# picoKey_230407.net
KiCad netlist of a schematic drawn in EAGLE
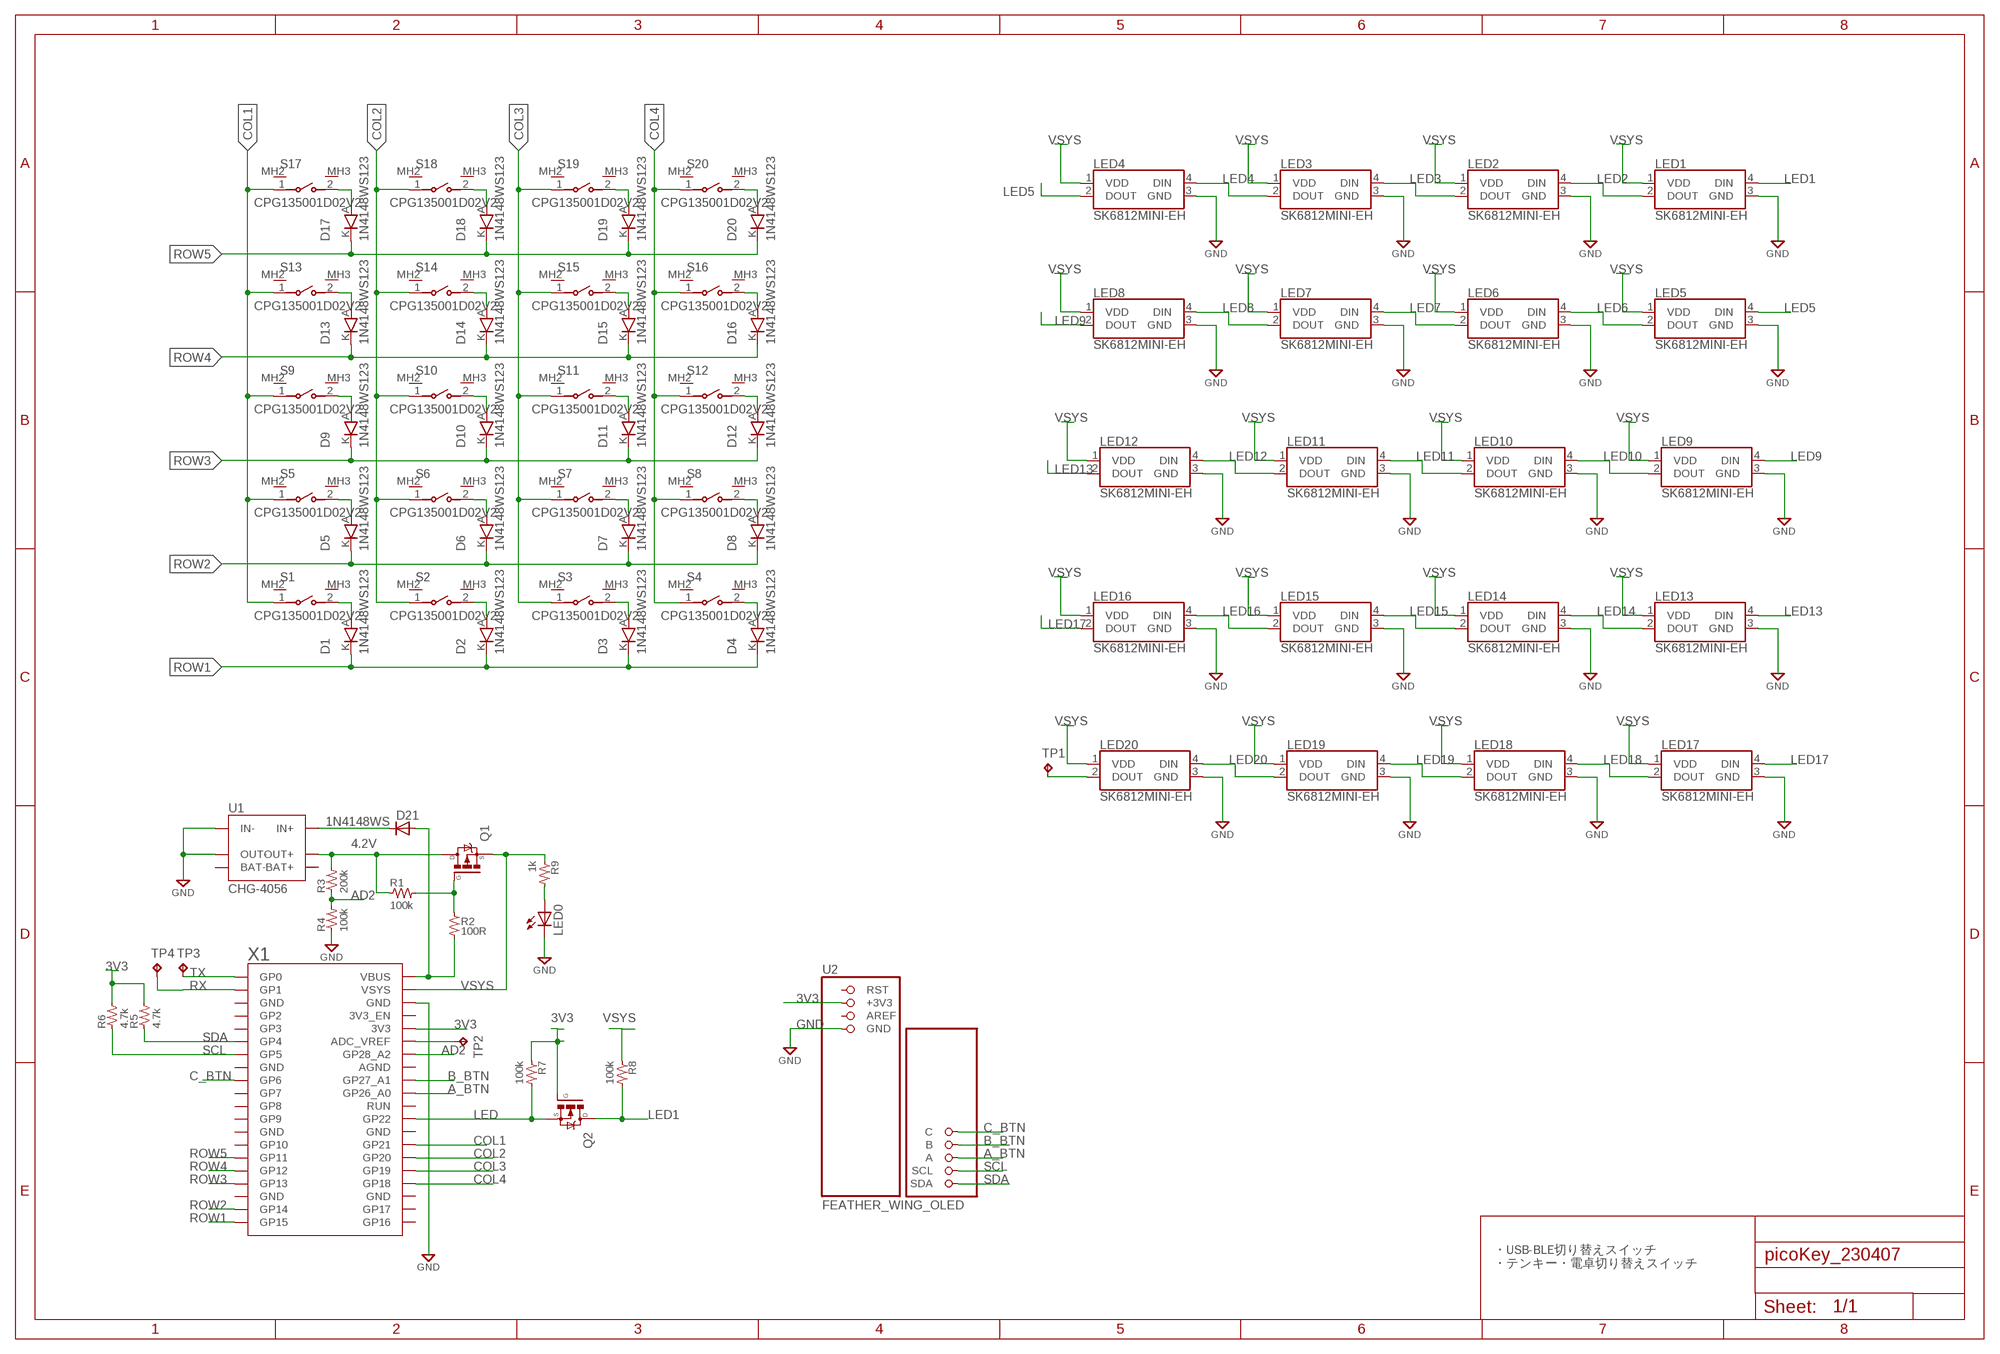
[diagram p0: schematic, sheet 1]

(export (version "E")
  (design (tool "Eeschema 10.0.6"))
  (components
    (comp (ref "D1")
      (value "1N4148WS123")
      (footprint "eagle-import:SOD-123")
      (libsource (lib "eagle-import") (part "1N4148WS123"))
    )
    (comp (ref "D2")
      (value "1N4148WS123")
      (footprint "eagle-import:SOD-123")
      (libsource (lib "eagle-import") (part "1N4148WS123"))
    )
    (comp (ref "D3")
      (value "1N4148WS123")
      (footprint "eagle-import:SOD-123")
      (libsource (lib "eagle-import") (part "1N4148WS123"))
    )
    (comp (ref "D4")
      (value "1N4148WS123")
      (footprint "eagle-import:SOD-123")
      (libsource (lib "eagle-import") (part "1N4148WS123"))
    )
    (comp (ref "D5")
      (value "1N4148WS123")
      (footprint "eagle-import:SOD-123")
      (libsource (lib "eagle-import") (part "1N4148WS123"))
    )
    (comp (ref "D6")
      (value "1N4148WS123")
      (footprint "eagle-import:SOD-123")
      (libsource (lib "eagle-import") (part "1N4148WS123"))
    )
    (comp (ref "D7")
      (value "1N4148WS123")
      (footprint "eagle-import:SOD-123")
      (libsource (lib "eagle-import") (part "1N4148WS123"))
    )
    (comp (ref "D8")
      (value "1N4148WS123")
      (footprint "eagle-import:SOD-123")
      (libsource (lib "eagle-import") (part "1N4148WS123"))
    )
    (comp (ref "D9")
      (value "1N4148WS123")
      (footprint "eagle-import:SOD-123")
      (libsource (lib "eagle-import") (part "1N4148WS123"))
    )
    (comp (ref "D10")
      (value "1N4148WS123")
      (footprint "eagle-import:SOD-123")
      (libsource (lib "eagle-import") (part "1N4148WS123"))
    )
    (comp (ref "D11")
      (value "1N4148WS123")
      (footprint "eagle-import:SOD-123")
      (libsource (lib "eagle-import") (part "1N4148WS123"))
    )
    (comp (ref "D12")
      (value "1N4148WS123")
      (footprint "eagle-import:SOD-123")
      (libsource (lib "eagle-import") (part "1N4148WS123"))
    )
    (comp (ref "D13")
      (value "1N4148WS123")
      (footprint "eagle-import:SOD-123")
      (libsource (lib "eagle-import") (part "1N4148WS123"))
    )
    (comp (ref "D14")
      (value "1N4148WS123")
      (footprint "eagle-import:SOD-123")
      (libsource (lib "eagle-import") (part "1N4148WS123"))
    )
    (comp (ref "D15")
      (value "1N4148WS123")
      (footprint "eagle-import:SOD-123")
      (libsource (lib "eagle-import") (part "1N4148WS123"))
    )
    (comp (ref "D16")
      (value "1N4148WS123")
      (footprint "eagle-import:SOD-123")
      (libsource (lib "eagle-import") (part "1N4148WS123"))
    )
    (comp (ref "D17")
      (value "1N4148WS123")
      (footprint "eagle-import:SOD-123")
      (libsource (lib "eagle-import") (part "1N4148WS123"))
    )
    (comp (ref "D18")
      (value "1N4148WS123")
      (footprint "eagle-import:SOD-123")
      (libsource (lib "eagle-import") (part "1N4148WS123"))
    )
    (comp (ref "D19")
      (value "1N4148WS123")
      (footprint "eagle-import:SOD-123")
      (libsource (lib "eagle-import") (part "1N4148WS123"))
    )
    (comp (ref "D20")
      (value "1N4148WS123")
      (footprint "eagle-import:SOD-123")
      (libsource (lib "eagle-import") (part "1N4148WS123"))
    )
    (comp (ref "D21")
      (value "1N4148WS")
      (footprint "eagle-import:SOD-123")
      (libsource (lib "eagle-import") (part "DIODE123"))
    )
    (comp (ref "LED0")
      (value "LEDCHIP-LED0603")
      (footprint "eagle-import:CHIP-LED0603")
      (libsource (lib "eagle-import") (part "LEDCHIP-LED0603"))
    )
    (comp (ref "LED1")
      (value "SK6812MINI-EH")
      (footprint "eagle-import:SK6812MINIE-H")
      (libsource (lib "eagle-import") (part "SK6812MINI-EH"))
    )
    (comp (ref "LED2")
      (value "SK6812MINI-EH")
      (footprint "eagle-import:SK6812MINIE-H")
      (libsource (lib "eagle-import") (part "SK6812MINI-EH"))
    )
    (comp (ref "LED3")
      (value "SK6812MINI-EH")
      (footprint "eagle-import:SK6812MINIE-H")
      (libsource (lib "eagle-import") (part "SK6812MINI-EH"))
    )
    (comp (ref "LED4")
      (value "SK6812MINI-EH")
      (footprint "eagle-import:SK6812MINIE-H")
      (libsource (lib "eagle-import") (part "SK6812MINI-EH"))
    )
    (comp (ref "LED5")
      (value "SK6812MINI-EH")
      (footprint "eagle-import:SK6812MINIE-H")
      (libsource (lib "eagle-import") (part "SK6812MINI-EH"))
    )
    (comp (ref "LED6")
      (value "SK6812MINI-EH")
      (footprint "eagle-import:SK6812MINIE-H")
      (libsource (lib "eagle-import") (part "SK6812MINI-EH"))
    )
    (comp (ref "LED7")
      (value "SK6812MINI-EH")
      (footprint "eagle-import:SK6812MINIE-H")
      (libsource (lib "eagle-import") (part "SK6812MINI-EH"))
    )
    (comp (ref "LED8")
      (value "SK6812MINI-EH")
      (footprint "eagle-import:SK6812MINIE-H")
      (libsource (lib "eagle-import") (part "SK6812MINI-EH"))
    )
    (comp (ref "LED9")
      (value "SK6812MINI-EH")
      (footprint "eagle-import:SK6812MINIE-H")
      (libsource (lib "eagle-import") (part "SK6812MINI-EH"))
    )
    (comp (ref "LED10")
      (value "SK6812MINI-EH")
      (footprint "eagle-import:SK6812MINIE-H")
      (libsource (lib "eagle-import") (part "SK6812MINI-EH"))
    )
    (comp (ref "LED11")
      (value "SK6812MINI-EH")
      (footprint "eagle-import:SK6812MINIE-H")
      (libsource (lib "eagle-import") (part "SK6812MINI-EH"))
    )
    (comp (ref "LED12")
      (value "SK6812MINI-EH")
      (footprint "eagle-import:SK6812MINIE-H")
      (libsource (lib "eagle-import") (part "SK6812MINI-EH"))
    )
    (comp (ref "LED13")
      (value "SK6812MINI-EH")
      (footprint "eagle-import:SK6812MINIE-H")
      (libsource (lib "eagle-import") (part "SK6812MINI-EH"))
    )
    (comp (ref "LED14")
      (value "SK6812MINI-EH")
      (footprint "eagle-import:SK6812MINIE-H")
      (libsource (lib "eagle-import") (part "SK6812MINI-EH"))
    )
    (comp (ref "LED15")
      (value "SK6812MINI-EH")
      (footprint "eagle-import:SK6812MINIE-H")
      (libsource (lib "eagle-import") (part "SK6812MINI-EH"))
    )
    (comp (ref "LED16")
      (value "SK6812MINI-EH")
      (footprint "eagle-import:SK6812MINIE-H")
      (libsource (lib "eagle-import") (part "SK6812MINI-EH"))
    )
    (comp (ref "LED17")
      (value "SK6812MINI-EH")
      (footprint "eagle-import:SK6812MINIE-H")
      (libsource (lib "eagle-import") (part "SK6812MINI-EH"))
    )
    (comp (ref "LED18")
      (value "SK6812MINI-EH")
      (footprint "eagle-import:SK6812MINIE-H")
      (libsource (lib "eagle-import") (part "SK6812MINI-EH"))
    )
    (comp (ref "LED19")
      (value "SK6812MINI-EH")
      (footprint "eagle-import:SK6812MINIE-H")
      (libsource (lib "eagle-import") (part "SK6812MINI-EH"))
    )
    (comp (ref "LED20")
      (value "SK6812MINI-EH")
      (footprint "eagle-import:SK6812MINIE-H")
      (libsource (lib "eagle-import") (part "SK6812MINI-EH"))
    )
    (comp (ref "Q1")
      (value "MOSFET-P")
      (footprint "eagle-import:SOT-23")
      (libsource (lib "eagle-import") (part "MOSFET-P"))
    )
    (comp (ref "Q2")
      (value "MOSFET-NSOT-23")
      (footprint "eagle-import:SOT-23")
      (libsource (lib "eagle-import") (part "MOSFET-NSOT-23"))
    )
    (comp (ref "R1")
      (value "100k")
      (footprint "eagle-import:R0603")
      (libsource (lib "eagle-import") (part "R_0603"))
    )
    (comp (ref "R2")
      (value "100R")
      (footprint "eagle-import:R0603")
      (libsource (lib "eagle-import") (part "R_0603"))
    )
    (comp (ref "R3")
      (value "200k")
      (footprint "eagle-import:R0603")
      (libsource (lib "eagle-import") (part "R_0603"))
    )
    (comp (ref "R4")
      (value "100k")
      (footprint "eagle-import:R0603")
      (libsource (lib "eagle-import") (part "R_0603"))
    )
    (comp (ref "R5")
      (value "4.7k")
      (footprint "eagle-import:R0603")
      (libsource (lib "eagle-import") (part "R_0603"))
    )
    (comp (ref "R6")
      (value "4.7k")
      (footprint "eagle-import:R0603")
      (libsource (lib "eagle-import") (part "R_0603"))
    )
    (comp (ref "R7")
      (value "100k")
      (footprint "eagle-import:R0603")
      (libsource (lib "eagle-import") (part "R_0603"))
    )
    (comp (ref "R8")
      (value "100k")
      (footprint "eagle-import:R0603")
      (libsource (lib "eagle-import") (part "R_0603"))
    )
    (comp (ref "R9")
      (value "1k")
      (footprint "eagle-import:R0603")
      (libsource (lib "eagle-import") (part "R_0603"))
    )
    (comp (ref "S1")
      (value "CPG135001D02V2")
      (footprint "eagle-import:KAILH_CHOC_V2")
      (libsource (lib "eagle-import") (part "CPG135001D02V2"))
    )
    (comp (ref "S2")
      (value "CPG135001D02V2")
      (footprint "eagle-import:KAILH_CHOC_V2")
      (libsource (lib "eagle-import") (part "CPG135001D02V2"))
    )
    (comp (ref "S3")
      (value "CPG135001D02V2")
      (footprint "eagle-import:KAILH_CHOC_V2")
      (libsource (lib "eagle-import") (part "CPG135001D02V2"))
    )
    (comp (ref "S4")
      (value "CPG135001D02V2")
      (footprint "eagle-import:KAILH_CHOC_V2")
      (libsource (lib "eagle-import") (part "CPG135001D02V2"))
    )
    (comp (ref "S5")
      (value "CPG135001D02V2")
      (footprint "eagle-import:KAILH_CHOC_V2")
      (libsource (lib "eagle-import") (part "CPG135001D02V2"))
    )
    (comp (ref "S6")
      (value "CPG135001D02V2")
      (footprint "eagle-import:KAILH_CHOC_V2")
      (libsource (lib "eagle-import") (part "CPG135001D02V2"))
    )
    (comp (ref "S7")
      (value "CPG135001D02V2")
      (footprint "eagle-import:KAILH_CHOC_V2")
      (libsource (lib "eagle-import") (part "CPG135001D02V2"))
    )
    (comp (ref "S8")
      (value "CPG135001D02V2")
      (footprint "eagle-import:KAILH_CHOC_V2")
      (libsource (lib "eagle-import") (part "CPG135001D02V2"))
    )
    (comp (ref "S9")
      (value "CPG135001D02V2")
      (footprint "eagle-import:KAILH_CHOC_V2")
      (libsource (lib "eagle-import") (part "CPG135001D02V2"))
    )
    (comp (ref "S10")
      (value "CPG135001D02V2")
      (footprint "eagle-import:KAILH_CHOC_V2")
      (libsource (lib "eagle-import") (part "CPG135001D02V2"))
    )
    (comp (ref "S11")
      (value "CPG135001D02V2")
      (footprint "eagle-import:KAILH_CHOC_V2")
      (libsource (lib "eagle-import") (part "CPG135001D02V2"))
    )
    (comp (ref "S12")
      (value "CPG135001D02V2")
      (footprint "eagle-import:KAILH_CHOC_V2")
      (libsource (lib "eagle-import") (part "CPG135001D02V2"))
    )
    (comp (ref "S13")
      (value "CPG135001D02V2")
      (footprint "eagle-import:KAILH_CHOC_V2")
      (libsource (lib "eagle-import") (part "CPG135001D02V2"))
    )
    (comp (ref "S14")
      (value "CPG135001D02V2")
      (footprint "eagle-import:KAILH_CHOC_V2")
      (libsource (lib "eagle-import") (part "CPG135001D02V2"))
    )
    (comp (ref "S15")
      (value "CPG135001D02V2")
      (footprint "eagle-import:KAILH_CHOC_V2")
      (libsource (lib "eagle-import") (part "CPG135001D02V2"))
    )
    (comp (ref "S16")
      (value "CPG135001D02V2")
      (footprint "eagle-import:KAILH_CHOC_V2")
      (libsource (lib "eagle-import") (part "CPG135001D02V2"))
    )
    (comp (ref "S17")
      (value "CPG135001D02V2")
      (footprint "eagle-import:KAILH_CHOC_V2")
      (libsource (lib "eagle-import") (part "CPG135001D02V2"))
    )
    (comp (ref "S18")
      (value "CPG135001D02V2")
      (footprint "eagle-import:KAILH_CHOC_V2")
      (libsource (lib "eagle-import") (part "CPG135001D02V2"))
    )
    (comp (ref "S19")
      (value "CPG135001D02V2")
      (footprint "eagle-import:KAILH_CHOC_V2")
      (libsource (lib "eagle-import") (part "CPG135001D02V2"))
    )
    (comp (ref "S20")
      (value "CPG135001D02V2")
      (footprint "eagle-import:KAILH_CHOC_V2")
      (libsource (lib "eagle-import") (part "CPG135001D02V2"))
    )
    (comp (ref "TP1")
      (value "TPTP06R")
      (footprint "eagle-import:TP06R")
      (libsource (lib "eagle-import") (part "TPTP06R"))
    )
    (comp (ref "TP2")
      (value "TPTP06R")
      (footprint "eagle-import:TP06R")
      (libsource (lib "eagle-import") (part "TPTP06R"))
    )
    (comp (ref "TP3")
      (value "TPTP06R")
      (footprint "eagle-import:TP06R")
      (libsource (lib "eagle-import") (part "TPTP06R"))
    )
    (comp (ref "TP4")
      (value "TPTP06R")
      (footprint "eagle-import:TP06R")
      (libsource (lib "eagle-import") (part "TPTP06R"))
    )
    (comp (ref "U1")
      (value "CHG-4056")
      (footprint "eagle-import:CHG-4056")
      (libsource (lib "eagle-import") (part "CHG-4056"))
    )
    (comp (ref "U2")
      (value "FEATHER_WING_OLED")
      (footprint "eagle-import:FEATHER_WING_OLED")
      (libsource (lib "eagle-import") (part "FEATHER_WING_OLED"))
    )
    (comp (ref "X1")
      (value "RASPBERRYPI_PICO_RPI_PICO_MY-MY")
      (footprint "eagle-import:RASPBERRYPI_PICO_RPI_PICO_MY")
      (libsource (lib "eagle-import") (part "RASPBERRYPI_PICO_RPI_PICO_MY-MY"))
    )
  )
  (nets
    (net (code "1") (name "/3V3") (class "Default")
      (node (ref "Q2") (pin "3") (pinfunction "G_3") (pintype "passive"))
      (node (ref "R5") (pin "2") (pinfunction "2_2") (pintype "passive"))
      (node (ref "R6") (pin "2") (pinfunction "2_2") (pintype "passive"))
      (node (ref "R7") (pin "1") (pinfunction "1_1") (pintype "passive"))
      (node (ref "U2") (pin "15") (pinfunction "+3V3_15") (pintype "passive"))
      (node (ref "X1") (pin "3V3") (pinfunction "3V3_3V3") (pintype "bidirectional"))
    )
    (net (code "2") (name "/4.2V") (class "Default")
      (node (ref "Q1") (pin "2") (pinfunction "D_2") (pintype "passive"))
      (node (ref "R1") (pin "1") (pinfunction "1_1") (pintype "passive"))
      (node (ref "R3") (pin "2") (pinfunction "2_2") (pintype "passive"))
      (node (ref "U1") (pin "OUT+") (pinfunction "OUT+_OUT+") (pintype "bidirectional"))
    )
    (net (code "3") (name "/AD2") (class "Default")
      (node (ref "R3") (pin "1") (pinfunction "1_1") (pintype "passive"))
      (node (ref "R4") (pin "2") (pinfunction "2_2") (pintype "passive"))
      (node (ref "X1") (pin "GP28_A2") (pinfunction "GP28_A2_GP28_A2") (pintype "bidirectional"))
    )
    (net (code "4") (name "/A_BTN") (class "Default")
      (node (ref "U2") (pin "26") (pinfunction "A_26") (pintype "passive"))
      (node (ref "X1") (pin "GP26_A0") (pinfunction "GP26_A0_GP26_A0") (pintype "bidirectional"))
    )
    (net (code "5") (name "/B_BTN") (class "Default")
      (node (ref "U2") (pin "25") (pinfunction "B_25") (pintype "passive"))
      (node (ref "X1") (pin "GP27_A1") (pinfunction "GP27_A1_GP27_A1") (pintype "bidirectional"))
    )
    (net (code "6") (name "/C_BTN") (class "Default")
      (node (ref "U2") (pin "24") (pinfunction "C_24") (pintype "passive"))
      (node (ref "X1") (pin "GP6") (pinfunction "GP6_GP6") (pintype "bidirectional"))
    )
    (net (code "7") (name "/LED") (class "Default")
      (node (ref "Q2") (pin "1") (pinfunction "S_1") (pintype "passive"))
      (node (ref "R7") (pin "2") (pinfunction "2_2") (pintype "passive"))
      (node (ref "X1") (pin "GP22") (pinfunction "GP22_GP22") (pintype "bidirectional"))
    )
    (net (code "8") (name "/LED1") (class "Default")
      (node (ref "LED1") (pin "4") (pinfunction "DIN_4") (pintype "bidirectional"))
      (node (ref "Q2") (pin "2") (pinfunction "D_2") (pintype "passive"))
      (node (ref "R8") (pin "2") (pinfunction "2_2") (pintype "passive"))
    )
    (net (code "9") (name "/LED2") (class "Default")
      (node (ref "LED1") (pin "2") (pinfunction "DOUT_2") (pintype "bidirectional"))
      (node (ref "LED2") (pin "4") (pinfunction "DIN_4") (pintype "bidirectional"))
    )
    (net (code "10") (name "/LED3") (class "Default")
      (node (ref "LED2") (pin "2") (pinfunction "DOUT_2") (pintype "bidirectional"))
      (node (ref "LED3") (pin "4") (pinfunction "DIN_4") (pintype "bidirectional"))
    )
    (net (code "11") (name "/LED4") (class "Default")
      (node (ref "LED3") (pin "2") (pinfunction "DOUT_2") (pintype "bidirectional"))
      (node (ref "LED4") (pin "4") (pinfunction "DIN_4") (pintype "bidirectional"))
    )
    (net (code "12") (name "/LED5") (class "Default")
      (node (ref "LED4") (pin "2") (pinfunction "DOUT_2") (pintype "bidirectional"))
      (node (ref "LED5") (pin "4") (pinfunction "DIN_4") (pintype "bidirectional"))
    )
    (net (code "13") (name "/LED6") (class "Default")
      (node (ref "LED5") (pin "2") (pinfunction "DOUT_2") (pintype "bidirectional"))
      (node (ref "LED6") (pin "4") (pinfunction "DIN_4") (pintype "bidirectional"))
    )
    (net (code "14") (name "/LED7") (class "Default")
      (node (ref "LED6") (pin "2") (pinfunction "DOUT_2") (pintype "bidirectional"))
      (node (ref "LED7") (pin "4") (pinfunction "DIN_4") (pintype "bidirectional"))
    )
    (net (code "15") (name "/LED8") (class "Default")
      (node (ref "LED7") (pin "2") (pinfunction "DOUT_2") (pintype "bidirectional"))
      (node (ref "LED8") (pin "4") (pinfunction "DIN_4") (pintype "bidirectional"))
    )
    (net (code "16") (name "/LED9") (class "Default")
      (node (ref "LED8") (pin "2") (pinfunction "DOUT_2") (pintype "bidirectional"))
      (node (ref "LED9") (pin "4") (pinfunction "DIN_4") (pintype "bidirectional"))
    )
    (net (code "17") (name "/LED10") (class "Default")
      (node (ref "LED10") (pin "4") (pinfunction "DIN_4") (pintype "bidirectional"))
      (node (ref "LED9") (pin "2") (pinfunction "DOUT_2") (pintype "bidirectional"))
    )
    (net (code "18") (name "/LED11") (class "Default")
      (node (ref "LED10") (pin "2") (pinfunction "DOUT_2") (pintype "bidirectional"))
      (node (ref "LED11") (pin "4") (pinfunction "DIN_4") (pintype "bidirectional"))
    )
    (net (code "19") (name "/LED12") (class "Default")
      (node (ref "LED11") (pin "2") (pinfunction "DOUT_2") (pintype "bidirectional"))
      (node (ref "LED12") (pin "4") (pinfunction "DIN_4") (pintype "bidirectional"))
    )
    (net (code "20") (name "/LED13") (class "Default")
      (node (ref "LED12") (pin "2") (pinfunction "DOUT_2") (pintype "bidirectional"))
      (node (ref "LED13") (pin "4") (pinfunction "DIN_4") (pintype "bidirectional"))
    )
    (net (code "21") (name "/LED14") (class "Default")
      (node (ref "LED13") (pin "2") (pinfunction "DOUT_2") (pintype "bidirectional"))
      (node (ref "LED14") (pin "4") (pinfunction "DIN_4") (pintype "bidirectional"))
    )
    (net (code "22") (name "/LED15") (class "Default")
      (node (ref "LED14") (pin "2") (pinfunction "DOUT_2") (pintype "bidirectional"))
      (node (ref "LED15") (pin "4") (pinfunction "DIN_4") (pintype "bidirectional"))
    )
    (net (code "23") (name "/LED16") (class "Default")
      (node (ref "LED15") (pin "2") (pinfunction "DOUT_2") (pintype "bidirectional"))
      (node (ref "LED16") (pin "4") (pinfunction "DIN_4") (pintype "bidirectional"))
    )
    (net (code "24") (name "/LED17") (class "Default")
      (node (ref "LED16") (pin "2") (pinfunction "DOUT_2") (pintype "bidirectional"))
      (node (ref "LED17") (pin "4") (pinfunction "DIN_4") (pintype "bidirectional"))
    )
    (net (code "25") (name "/LED18") (class "Default")
      (node (ref "LED17") (pin "2") (pinfunction "DOUT_2") (pintype "bidirectional"))
      (node (ref "LED18") (pin "4") (pinfunction "DIN_4") (pintype "bidirectional"))
    )
    (net (code "26") (name "/LED19") (class "Default")
      (node (ref "LED18") (pin "2") (pinfunction "DOUT_2") (pintype "bidirectional"))
      (node (ref "LED19") (pin "4") (pinfunction "DIN_4") (pintype "bidirectional"))
    )
    (net (code "27") (name "/LED20") (class "Default")
      (node (ref "LED19") (pin "2") (pinfunction "DOUT_2") (pintype "bidirectional"))
      (node (ref "LED20") (pin "4") (pinfunction "DIN_4") (pintype "bidirectional"))
    )
    (net (code "28") (name "/RX") (class "Default")
      (node (ref "TP4") (pin "TP") (pinfunction "TP_TP") (pintype "input"))
      (node (ref "X1") (pin "GP1") (pinfunction "GP1_GP1") (pintype "bidirectional"))
    )
    (net (code "29") (name "/SCL") (class "Default")
      (node (ref "R6") (pin "1") (pinfunction "1_1") (pintype "passive"))
      (node (ref "U2") (pin "27") (pinfunction "SCL_27") (pintype "passive"))
      (node (ref "X1") (pin "GP5") (pinfunction "GP5_GP5") (pintype "bidirectional"))
    )
    (net (code "30") (name "/SDA") (class "Default")
      (node (ref "R5") (pin "1") (pinfunction "1_1") (pintype "passive"))
      (node (ref "U2") (pin "28") (pinfunction "SDA_28") (pintype "passive"))
      (node (ref "X1") (pin "GP4") (pinfunction "GP4_GP4") (pintype "bidirectional"))
    )
    (net (code "31") (name "/TX") (class "Default")
      (node (ref "TP3") (pin "TP") (pinfunction "TP_TP") (pintype "input"))
      (node (ref "X1") (pin "GP0") (pinfunction "GP0_GP0") (pintype "bidirectional"))
    )
    (net (code "32") (name "/VSYS") (class "Default")
      (node (ref "LED1") (pin "1") (pinfunction "VDD_1") (pintype "bidirectional"))
      (node (ref "LED10") (pin "1") (pinfunction "VDD_1") (pintype "bidirectional"))
      (node (ref "LED11") (pin "1") (pinfunction "VDD_1") (pintype "bidirectional"))
      (node (ref "LED12") (pin "1") (pinfunction "VDD_1") (pintype "bidirectional"))
      (node (ref "LED13") (pin "1") (pinfunction "VDD_1") (pintype "bidirectional"))
      (node (ref "LED14") (pin "1") (pinfunction "VDD_1") (pintype "bidirectional"))
      (node (ref "LED15") (pin "1") (pinfunction "VDD_1") (pintype "bidirectional"))
      (node (ref "LED16") (pin "1") (pinfunction "VDD_1") (pintype "bidirectional"))
      (node (ref "LED17") (pin "1") (pinfunction "VDD_1") (pintype "bidirectional"))
      (node (ref "LED18") (pin "1") (pinfunction "VDD_1") (pintype "bidirectional"))
      (node (ref "LED19") (pin "1") (pinfunction "VDD_1") (pintype "bidirectional"))
      (node (ref "LED2") (pin "1") (pinfunction "VDD_1") (pintype "bidirectional"))
      (node (ref "LED20") (pin "1") (pinfunction "VDD_1") (pintype "bidirectional"))
      (node (ref "LED3") (pin "1") (pinfunction "VDD_1") (pintype "bidirectional"))
      (node (ref "LED4") (pin "1") (pinfunction "VDD_1") (pintype "bidirectional"))
      (node (ref "LED5") (pin "1") (pinfunction "VDD_1") (pintype "bidirectional"))
      (node (ref "LED6") (pin "1") (pinfunction "VDD_1") (pintype "bidirectional"))
      (node (ref "LED7") (pin "1") (pinfunction "VDD_1") (pintype "bidirectional"))
      (node (ref "LED8") (pin "1") (pinfunction "VDD_1") (pintype "bidirectional"))
      (node (ref "LED9") (pin "1") (pinfunction "VDD_1") (pintype "bidirectional"))
      (node (ref "Q1") (pin "1") (pinfunction "S_1") (pintype "passive"))
      (node (ref "R8") (pin "1") (pinfunction "1_1") (pintype "passive"))
      (node (ref "R9") (pin "1") (pinfunction "1_1") (pintype "passive"))
      (node (ref "X1") (pin "VSYS") (pinfunction "VSYS_VSYS") (pintype "bidirectional"))
    )
    (net (code "33") (name "COL1") (class "Default")
      (node (ref "S1") (pin "1") (pinfunction "1_1") (pintype "bidirectional"))
      (node (ref "S13") (pin "1") (pinfunction "1_1") (pintype "bidirectional"))
      (node (ref "S17") (pin "1") (pinfunction "1_1") (pintype "bidirectional"))
      (node (ref "S5") (pin "1") (pinfunction "1_1") (pintype "bidirectional"))
      (node (ref "S9") (pin "1") (pinfunction "1_1") (pintype "bidirectional"))
      (node (ref "X1") (pin "GP21") (pinfunction "GP21_GP21") (pintype "bidirectional"))
    )
    (net (code "34") (name "COL2") (class "Default")
      (node (ref "S10") (pin "1") (pinfunction "1_1") (pintype "bidirectional"))
      (node (ref "S14") (pin "1") (pinfunction "1_1") (pintype "bidirectional"))
      (node (ref "S18") (pin "1") (pinfunction "1_1") (pintype "bidirectional"))
      (node (ref "S2") (pin "1") (pinfunction "1_1") (pintype "bidirectional"))
      (node (ref "S6") (pin "1") (pinfunction "1_1") (pintype "bidirectional"))
      (node (ref "X1") (pin "GP20") (pinfunction "GP20_GP20") (pintype "bidirectional"))
    )
    (net (code "35") (name "COL3") (class "Default")
      (node (ref "S11") (pin "1") (pinfunction "1_1") (pintype "bidirectional"))
      (node (ref "S15") (pin "1") (pinfunction "1_1") (pintype "bidirectional"))
      (node (ref "S19") (pin "1") (pinfunction "1_1") (pintype "bidirectional"))
      (node (ref "S3") (pin "1") (pinfunction "1_1") (pintype "bidirectional"))
      (node (ref "S7") (pin "1") (pinfunction "1_1") (pintype "bidirectional"))
      (node (ref "X1") (pin "GP19") (pinfunction "GP19_GP19") (pintype "bidirectional"))
    )
    (net (code "36") (name "COL4") (class "Default")
      (node (ref "S12") (pin "1") (pinfunction "1_1") (pintype "bidirectional"))
      (node (ref "S16") (pin "1") (pinfunction "1_1") (pintype "bidirectional"))
      (node (ref "S20") (pin "1") (pinfunction "1_1") (pintype "bidirectional"))
      (node (ref "S4") (pin "1") (pinfunction "1_1") (pintype "bidirectional"))
      (node (ref "S8") (pin "1") (pinfunction "1_1") (pintype "bidirectional"))
      (node (ref "X1") (pin "GP18") (pinfunction "GP18_GP18") (pintype "bidirectional"))
    )
    (net (code "37") (name "G") (class "Default")
      (node (ref "LED0") (pin "C") (pinfunction "C_C") (pintype "passive"))
      (node (ref "LED1") (pin "3") (pinfunction "GND_3") (pintype "bidirectional"))
      (node (ref "LED10") (pin "3") (pinfunction "GND_3") (pintype "bidirectional"))
      (node (ref "LED11") (pin "3") (pinfunction "GND_3") (pintype "bidirectional"))
      (node (ref "LED12") (pin "3") (pinfunction "GND_3") (pintype "bidirectional"))
      (node (ref "LED13") (pin "3") (pinfunction "GND_3") (pintype "bidirectional"))
      (node (ref "LED14") (pin "3") (pinfunction "GND_3") (pintype "bidirectional"))
      (node (ref "LED15") (pin "3") (pinfunction "GND_3") (pintype "bidirectional"))
      (node (ref "LED16") (pin "3") (pinfunction "GND_3") (pintype "bidirectional"))
      (node (ref "LED17") (pin "3") (pinfunction "GND_3") (pintype "bidirectional"))
      (node (ref "LED18") (pin "3") (pinfunction "GND_3") (pintype "bidirectional"))
      (node (ref "LED19") (pin "3") (pinfunction "GND_3") (pintype "bidirectional"))
      (node (ref "LED2") (pin "3") (pinfunction "GND_3") (pintype "bidirectional"))
      (node (ref "LED20") (pin "3") (pinfunction "GND_3") (pintype "bidirectional"))
      (node (ref "LED3") (pin "3") (pinfunction "GND_3") (pintype "bidirectional"))
      (node (ref "LED4") (pin "3") (pinfunction "GND_3") (pintype "bidirectional"))
      (node (ref "LED5") (pin "3") (pinfunction "GND_3") (pintype "bidirectional"))
      (node (ref "LED6") (pin "3") (pinfunction "GND_3") (pintype "bidirectional"))
      (node (ref "LED7") (pin "3") (pinfunction "GND_3") (pintype "bidirectional"))
      (node (ref "LED8") (pin "3") (pinfunction "GND_3") (pintype "bidirectional"))
      (node (ref "LED9") (pin "3") (pinfunction "GND_3") (pintype "bidirectional"))
      (node (ref "R4") (pin "1") (pinfunction "1_1") (pintype "passive"))
      (node (ref "U1") (pin "IN-") (pinfunction "IN-_IN-") (pintype "bidirectional"))
      (node (ref "U1") (pin "OUT-") (pinfunction "OUT-_OUT-") (pintype "bidirectional"))
      (node (ref "U2") (pin "13") (pinfunction "GND_13") (pintype "passive"))
      (node (ref "X1") (pin "GND@8") (pinfunction "GND_GND@8") (pintype "bidirectional"))
    )
    (net (code "38") (name "Net-(D1-PadA)") (class "Default")
      (node (ref "D1") (pin "A") (pinfunction "A_A") (pintype "bidirectional"))
      (node (ref "S1") (pin "2") (pinfunction "2_2") (pintype "bidirectional"))
    )
    (net (code "39") (name "Net-(D2-PadA)") (class "Default")
      (node (ref "D2") (pin "A") (pinfunction "A_A") (pintype "bidirectional"))
      (node (ref "S2") (pin "2") (pinfunction "2_2") (pintype "bidirectional"))
    )
    (net (code "40") (name "Net-(D3-PadA)") (class "Default")
      (node (ref "D3") (pin "A") (pinfunction "A_A") (pintype "bidirectional"))
      (node (ref "S3") (pin "2") (pinfunction "2_2") (pintype "bidirectional"))
    )
    (net (code "41") (name "Net-(D4-PadA)") (class "Default")
      (node (ref "D4") (pin "A") (pinfunction "A_A") (pintype "bidirectional"))
      (node (ref "S4") (pin "2") (pinfunction "2_2") (pintype "bidirectional"))
    )
    (net (code "42") (name "Net-(D5-PadA)") (class "Default")
      (node (ref "D5") (pin "A") (pinfunction "A_A") (pintype "bidirectional"))
      (node (ref "S5") (pin "2") (pinfunction "2_2") (pintype "bidirectional"))
    )
    (net (code "43") (name "Net-(D6-PadA)") (class "Default")
      (node (ref "D6") (pin "A") (pinfunction "A_A") (pintype "bidirectional"))
      (node (ref "S6") (pin "2") (pinfunction "2_2") (pintype "bidirectional"))
    )
    (net (code "44") (name "Net-(D7-PadA)") (class "Default")
      (node (ref "D7") (pin "A") (pinfunction "A_A") (pintype "bidirectional"))
      (node (ref "S7") (pin "2") (pinfunction "2_2") (pintype "bidirectional"))
    )
    (net (code "45") (name "Net-(D8-PadA)") (class "Default")
      (node (ref "D8") (pin "A") (pinfunction "A_A") (pintype "bidirectional"))
      (node (ref "S8") (pin "2") (pinfunction "2_2") (pintype "bidirectional"))
    )
    (net (code "46") (name "Net-(D9-PadA)") (class "Default")
      (node (ref "D9") (pin "A") (pinfunction "A_A") (pintype "bidirectional"))
      (node (ref "S9") (pin "2") (pinfunction "2_2") (pintype "bidirectional"))
    )
    (net (code "47") (name "Net-(D10-PadA)") (class "Default")
      (node (ref "D10") (pin "A") (pinfunction "A_A") (pintype "bidirectional"))
      (node (ref "S10") (pin "2") (pinfunction "2_2") (pintype "bidirectional"))
    )
    (net (code "48") (name "Net-(D11-PadA)") (class "Default")
      (node (ref "D11") (pin "A") (pinfunction "A_A") (pintype "bidirectional"))
      (node (ref "S11") (pin "2") (pinfunction "2_2") (pintype "bidirectional"))
    )
    (net (code "49") (name "Net-(D12-PadA)") (class "Default")
      (node (ref "D12") (pin "A") (pinfunction "A_A") (pintype "bidirectional"))
      (node (ref "S12") (pin "2") (pinfunction "2_2") (pintype "bidirectional"))
    )
    (net (code "50") (name "Net-(D13-PadA)") (class "Default")
      (node (ref "D13") (pin "A") (pinfunction "A_A") (pintype "bidirectional"))
      (node (ref "S13") (pin "2") (pinfunction "2_2") (pintype "bidirectional"))
    )
    (net (code "51") (name "Net-(D14-PadA)") (class "Default")
      (node (ref "D14") (pin "A") (pinfunction "A_A") (pintype "bidirectional"))
      (node (ref "S14") (pin "2") (pinfunction "2_2") (pintype "bidirectional"))
    )
    (net (code "52") (name "Net-(D15-PadA)") (class "Default")
      (node (ref "D15") (pin "A") (pinfunction "A_A") (pintype "bidirectional"))
      (node (ref "S15") (pin "2") (pinfunction "2_2") (pintype "bidirectional"))
    )
    (net (code "53") (name "Net-(D16-PadA)") (class "Default")
      (node (ref "D16") (pin "A") (pinfunction "A_A") (pintype "bidirectional"))
      (node (ref "S16") (pin "2") (pinfunction "2_2") (pintype "bidirectional"))
    )
    (net (code "54") (name "Net-(D17-PadA)") (class "Default")
      (node (ref "D17") (pin "A") (pinfunction "A_A") (pintype "bidirectional"))
      (node (ref "S17") (pin "2") (pinfunction "2_2") (pintype "bidirectional"))
    )
    (net (code "55") (name "Net-(D18-PadA)") (class "Default")
      (node (ref "D18") (pin "A") (pinfunction "A_A") (pintype "bidirectional"))
      (node (ref "S18") (pin "2") (pinfunction "2_2") (pintype "bidirectional"))
    )
    (net (code "56") (name "Net-(D19-PadA)") (class "Default")
      (node (ref "D19") (pin "A") (pinfunction "A_A") (pintype "bidirectional"))
      (node (ref "S19") (pin "2") (pinfunction "2_2") (pintype "bidirectional"))
    )
    (net (code "57") (name "Net-(D20-PadA)") (class "Default")
      (node (ref "D20") (pin "A") (pinfunction "A_A") (pintype "bidirectional"))
      (node (ref "S20") (pin "2") (pinfunction "2_2") (pintype "bidirectional"))
    )
    (net (code "58") (name "Net-(D21-C)") (class "Default")
      (node (ref "D21") (pin "K") (pinfunction "C_K") (pintype "passive"))
      (node (ref "U1") (pin "IN+") (pinfunction "IN+_IN+") (pintype "bidirectional"))
    )
    (net (code "59") (name "Net-(D21-PadA)") (class "Default")
      (node (ref "D21") (pin "A") (pinfunction "A_A") (pintype "passive"))
      (node (ref "R2") (pin "2") (pinfunction "2_2") (pintype "passive"))
      (node (ref "X1") (pin "VBUS") (pinfunction "VBUS_VBUS") (pintype "bidirectional"))
    )
    (net (code "60") (name "Net-(LED0-PadA)") (class "Default")
      (node (ref "LED0") (pin "A") (pinfunction "A_A") (pintype "passive"))
      (node (ref "R9") (pin "2") (pinfunction "2_2") (pintype "passive"))
    )
    (net (code "61") (name "Net-(LED20-DOUT)") (class "Default")
      (node (ref "LED20") (pin "2") (pinfunction "DOUT_2") (pintype "bidirectional"))
      (node (ref "TP1") (pin "TP") (pinfunction "TP_TP") (pintype "input"))
    )
    (net (code "62") (name "Net-(Q1-G)") (class "Default")
      (node (ref "Q1") (pin "3") (pinfunction "G_3") (pintype "passive"))
      (node (ref "R1") (pin "2") (pinfunction "2_2") (pintype "passive"))
      (node (ref "R2") (pin "1") (pinfunction "1_1") (pintype "passive"))
    )
    (net (code "63") (name "Net-(TP2-PadTP)") (class "Default")
      (node (ref "TP2") (pin "TP") (pinfunction "TP_TP") (pintype "input"))
      (node (ref "X1") (pin "ADC_VREF") (pinfunction "ADC_VREF_ADC_VREF") (pintype "bidirectional"))
    )
    (net (code "64") (name "ROW1") (class "Default")
      (node (ref "D1") (pin "K") (pinfunction "K_K") (pintype "bidirectional"))
      (node (ref "D2") (pin "K") (pinfunction "K_K") (pintype "bidirectional"))
      (node (ref "D3") (pin "K") (pinfunction "K_K") (pintype "bidirectional"))
      (node (ref "D4") (pin "K") (pinfunction "K_K") (pintype "bidirectional"))
      (node (ref "X1") (pin "GP15") (pinfunction "GP15_GP15") (pintype "bidirectional"))
    )
    (net (code "65") (name "ROW2") (class "Default")
      (node (ref "D5") (pin "K") (pinfunction "K_K") (pintype "bidirectional"))
      (node (ref "D6") (pin "K") (pinfunction "K_K") (pintype "bidirectional"))
      (node (ref "D7") (pin "K") (pinfunction "K_K") (pintype "bidirectional"))
      (node (ref "D8") (pin "K") (pinfunction "K_K") (pintype "bidirectional"))
      (node (ref "X1") (pin "GP14") (pinfunction "GP14_GP14") (pintype "bidirectional"))
    )
    (net (code "66") (name "ROW3") (class "Default")
      (node (ref "D10") (pin "K") (pinfunction "K_K") (pintype "bidirectional"))
      (node (ref "D11") (pin "K") (pinfunction "K_K") (pintype "bidirectional"))
      (node (ref "D12") (pin "K") (pinfunction "K_K") (pintype "bidirectional"))
      (node (ref "D9") (pin "K") (pinfunction "K_K") (pintype "bidirectional"))
      (node (ref "X1") (pin "GP13") (pinfunction "GP13_GP13") (pintype "bidirectional"))
    )
    (net (code "67") (name "ROW4") (class "Default")
      (node (ref "D13") (pin "K") (pinfunction "K_K") (pintype "bidirectional"))
      (node (ref "D14") (pin "K") (pinfunction "K_K") (pintype "bidirectional"))
      (node (ref "D15") (pin "K") (pinfunction "K_K") (pintype "bidirectional"))
      (node (ref "D16") (pin "K") (pinfunction "K_K") (pintype "bidirectional"))
      (node (ref "X1") (pin "GP12") (pinfunction "GP12_GP12") (pintype "bidirectional"))
    )
    (net (code "68") (name "ROW5") (class "Default")
      (node (ref "D17") (pin "K") (pinfunction "K_K") (pintype "bidirectional"))
      (node (ref "D18") (pin "K") (pinfunction "K_K") (pintype "bidirectional"))
      (node (ref "D19") (pin "K") (pinfunction "K_K") (pintype "bidirectional"))
      (node (ref "D20") (pin "K") (pinfunction "K_K") (pintype "bidirectional"))
      (node (ref "X1") (pin "GP11") (pinfunction "GP11_GP11") (pintype "bidirectional"))
    )
    (net (code "69") (name "unconnected-(S1-MH-PadMH2)") (class "Default")
      (node (ref "S1") (pin "MH2") (pinfunction "MH_MH2") (pintype "bidirectional"))
    )
    (net (code "70") (name "unconnected-(S1-MH-PadMH3)") (class "Default")
      (node (ref "S1") (pin "MH3") (pinfunction "MH_MH3") (pintype "bidirectional"))
    )
    (net (code "71") (name "unconnected-(S2-MH-PadMH2)") (class "Default")
      (node (ref "S2") (pin "MH2") (pinfunction "MH_MH2") (pintype "bidirectional"))
    )
    (net (code "72") (name "unconnected-(S2-MH-PadMH3)") (class "Default")
      (node (ref "S2") (pin "MH3") (pinfunction "MH_MH3") (pintype "bidirectional"))
    )
    (net (code "73") (name "unconnected-(S3-MH-PadMH2)") (class "Default")
      (node (ref "S3") (pin "MH2") (pinfunction "MH_MH2") (pintype "bidirectional"))
    )
    (net (code "74") (name "unconnected-(S3-MH-PadMH3)") (class "Default")
      (node (ref "S3") (pin "MH3") (pinfunction "MH_MH3") (pintype "bidirectional"))
    )
    (net (code "75") (name "unconnected-(S4-MH-PadMH2)") (class "Default")
      (node (ref "S4") (pin "MH2") (pinfunction "MH_MH2") (pintype "bidirectional"))
    )
    (net (code "76") (name "unconnected-(S4-MH-PadMH3)") (class "Default")
      (node (ref "S4") (pin "MH3") (pinfunction "MH_MH3") (pintype "bidirectional"))
    )
    (net (code "77") (name "unconnected-(S5-MH-PadMH2)") (class "Default")
      (node (ref "S5") (pin "MH2") (pinfunction "MH_MH2") (pintype "bidirectional"))
    )
    (net (code "78") (name "unconnected-(S5-MH-PadMH3)") (class "Default")
      (node (ref "S5") (pin "MH3") (pinfunction "MH_MH3") (pintype "bidirectional"))
    )
    (net (code "79") (name "unconnected-(S6-MH-PadMH2)") (class "Default")
      (node (ref "S6") (pin "MH2") (pinfunction "MH_MH2") (pintype "bidirectional"))
    )
    (net (code "80") (name "unconnected-(S6-MH-PadMH3)") (class "Default")
      (node (ref "S6") (pin "MH3") (pinfunction "MH_MH3") (pintype "bidirectional"))
    )
    (net (code "81") (name "unconnected-(S7-MH-PadMH2)") (class "Default")
      (node (ref "S7") (pin "MH2") (pinfunction "MH_MH2") (pintype "bidirectional"))
    )
    (net (code "82") (name "unconnected-(S7-MH-PadMH3)") (class "Default")
      (node (ref "S7") (pin "MH3") (pinfunction "MH_MH3") (pintype "bidirectional"))
    )
    (net (code "83") (name "unconnected-(S8-MH-PadMH2)") (class "Default")
      (node (ref "S8") (pin "MH2") (pinfunction "MH_MH2") (pintype "bidirectional"))
    )
    (net (code "84") (name "unconnected-(S8-MH-PadMH3)") (class "Default")
      (node (ref "S8") (pin "MH3") (pinfunction "MH_MH3") (pintype "bidirectional"))
    )
    (net (code "85") (name "unconnected-(S9-MH-PadMH2)") (class "Default")
      (node (ref "S9") (pin "MH2") (pinfunction "MH_MH2") (pintype "bidirectional"))
    )
    (net (code "86") (name "unconnected-(S9-MH-PadMH3)") (class "Default")
      (node (ref "S9") (pin "MH3") (pinfunction "MH_MH3") (pintype "bidirectional"))
    )
    (net (code "87") (name "unconnected-(S10-MH-PadMH2)") (class "Default")
      (node (ref "S10") (pin "MH2") (pinfunction "MH_MH2") (pintype "bidirectional"))
    )
    (net (code "88") (name "unconnected-(S10-MH-PadMH3)") (class "Default")
      (node (ref "S10") (pin "MH3") (pinfunction "MH_MH3") (pintype "bidirectional"))
    )
    (net (code "89") (name "unconnected-(S11-MH-PadMH2)") (class "Default")
      (node (ref "S11") (pin "MH2") (pinfunction "MH_MH2") (pintype "bidirectional"))
    )
    (net (code "90") (name "unconnected-(S11-MH-PadMH3)") (class "Default")
      (node (ref "S11") (pin "MH3") (pinfunction "MH_MH3") (pintype "bidirectional"))
    )
    (net (code "91") (name "unconnected-(S12-MH-PadMH2)") (class "Default")
      (node (ref "S12") (pin "MH2") (pinfunction "MH_MH2") (pintype "bidirectional"))
    )
    (net (code "92") (name "unconnected-(S12-MH-PadMH3)") (class "Default")
      (node (ref "S12") (pin "MH3") (pinfunction "MH_MH3") (pintype "bidirectional"))
    )
    (net (code "93") (name "unconnected-(S13-MH-PadMH2)") (class "Default")
      (node (ref "S13") (pin "MH2") (pinfunction "MH_MH2") (pintype "bidirectional"))
    )
    (net (code "94") (name "unconnected-(S13-MH-PadMH3)") (class "Default")
      (node (ref "S13") (pin "MH3") (pinfunction "MH_MH3") (pintype "bidirectional"))
    )
    (net (code "95") (name "unconnected-(S14-MH-PadMH2)") (class "Default")
      (node (ref "S14") (pin "MH2") (pinfunction "MH_MH2") (pintype "bidirectional"))
    )
    (net (code "96") (name "unconnected-(S14-MH-PadMH3)") (class "Default")
      (node (ref "S14") (pin "MH3") (pinfunction "MH_MH3") (pintype "bidirectional"))
    )
    (net (code "97") (name "unconnected-(S15-MH-PadMH2)") (class "Default")
      (node (ref "S15") (pin "MH2") (pinfunction "MH_MH2") (pintype "bidirectional"))
    )
    (net (code "98") (name "unconnected-(S15-MH-PadMH3)") (class "Default")
      (node (ref "S15") (pin "MH3") (pinfunction "MH_MH3") (pintype "bidirectional"))
    )
    (net (code "99") (name "unconnected-(S16-MH-PadMH2)") (class "Default")
      (node (ref "S16") (pin "MH2") (pinfunction "MH_MH2") (pintype "bidirectional"))
    )
    (net (code "100") (name "unconnected-(S16-MH-PadMH3)") (class "Default")
      (node (ref "S16") (pin "MH3") (pinfunction "MH_MH3") (pintype "bidirectional"))
    )
    (net (code "101") (name "unconnected-(S17-MH-PadMH2)") (class "Default")
      (node (ref "S17") (pin "MH2") (pinfunction "MH_MH2") (pintype "bidirectional"))
    )
    (net (code "102") (name "unconnected-(S17-MH-PadMH3)") (class "Default")
      (node (ref "S17") (pin "MH3") (pinfunction "MH_MH3") (pintype "bidirectional"))
    )
    (net (code "103") (name "unconnected-(S18-MH-PadMH2)") (class "Default")
      (node (ref "S18") (pin "MH2") (pinfunction "MH_MH2") (pintype "bidirectional"))
    )
    (net (code "104") (name "unconnected-(S18-MH-PadMH3)") (class "Default")
      (node (ref "S18") (pin "MH3") (pinfunction "MH_MH3") (pintype "bidirectional"))
    )
    (net (code "105") (name "unconnected-(S19-MH-PadMH2)") (class "Default")
      (node (ref "S19") (pin "MH2") (pinfunction "MH_MH2") (pintype "bidirectional"))
    )
    (net (code "106") (name "unconnected-(S19-MH-PadMH3)") (class "Default")
      (node (ref "S19") (pin "MH3") (pinfunction "MH_MH3") (pintype "bidirectional"))
    )
    (net (code "107") (name "unconnected-(S20-MH-PadMH2)") (class "Default")
      (node (ref "S20") (pin "MH2") (pinfunction "MH_MH2") (pintype "bidirectional"))
    )
    (net (code "108") (name "unconnected-(S20-MH-PadMH3)") (class "Default")
      (node (ref "S20") (pin "MH3") (pinfunction "MH_MH3") (pintype "bidirectional"))
    )
    (net (code "109") (name "unconnected-(U1-PadBAT+)") (class "Default")
      (node (ref "U1") (pin "BAT+") (pinfunction "BAT+_BAT+") (pintype "bidirectional"))
    )
    (net (code "110") (name "unconnected-(U1-PadBAT-)") (class "Default")
      (node (ref "U1") (pin "BAT-") (pinfunction "BAT-_BAT-") (pintype "bidirectional"))
    )
    (net (code "111") (name "unconnected-(U2-AREF-Pad14)") (class "Default")
      (node (ref "U2") (pin "14") (pinfunction "AREF_14") (pintype "passive"))
    )
    (net (code "112") (name "unconnected-(U2-RST-Pad16)") (class "Default")
      (node (ref "U2") (pin "16") (pinfunction "RST_16") (pintype "passive"))
    )
    (net (code "113") (name "unconnected-(X1-GND-PadGND@1)") (class "Default")
      (node (ref "X1") (pin "GND@1") (pinfunction "GND_GND@1") (pintype "bidirectional"))
    )
    (net (code "114") (name "unconnected-(X1-GND-PadGND@2)") (class "Default")
      (node (ref "X1") (pin "GND@2") (pinfunction "GND_GND@2") (pintype "bidirectional"))
    )
    (net (code "115") (name "unconnected-(X1-GND-PadGND@3)") (class "Default")
      (node (ref "X1") (pin "GND@3") (pinfunction "GND_GND@3") (pintype "bidirectional"))
    )
    (net (code "116") (name "unconnected-(X1-GND-PadGND@4)") (class "Default")
      (node (ref "X1") (pin "GND@4") (pinfunction "GND_GND@4") (pintype "bidirectional"))
    )
    (net (code "117") (name "unconnected-(X1-GND-PadGND@6)") (class "Default")
      (node (ref "X1") (pin "GND@6") (pinfunction "GND_GND@6") (pintype "bidirectional"))
    )
    (net (code "118") (name "unconnected-(X1-GND-PadGND@7)") (class "Default")
      (node (ref "X1") (pin "GND@7") (pinfunction "GND_GND@7") (pintype "bidirectional"))
    )
    (net (code "119") (name "unconnected-(X1-Pad3V3_EN)") (class "Default")
      (node (ref "X1") (pin "3V3_EN") (pinfunction "3V3_EN_3V3_EN") (pintype "bidirectional"))
    )
    (net (code "120") (name "unconnected-(X1-PadAGND)") (class "Default")
      (node (ref "X1") (pin "AGND") (pinfunction "AGND_AGND") (pintype "bidirectional"))
    )
    (net (code "121") (name "unconnected-(X1-PadGP2)") (class "Default")
      (node (ref "X1") (pin "GP2") (pinfunction "GP2_GP2") (pintype "bidirectional"))
    )
    (net (code "122") (name "unconnected-(X1-PadGP3)") (class "Default")
      (node (ref "X1") (pin "GP3") (pinfunction "GP3_GP3") (pintype "bidirectional"))
    )
    (net (code "123") (name "unconnected-(X1-PadGP7)") (class "Default")
      (node (ref "X1") (pin "GP7") (pinfunction "GP7_GP7") (pintype "bidirectional"))
    )
    (net (code "124") (name "unconnected-(X1-PadGP8)") (class "Default")
      (node (ref "X1") (pin "GP8") (pinfunction "GP8_GP8") (pintype "bidirectional"))
    )
    (net (code "125") (name "unconnected-(X1-PadGP9)") (class "Default")
      (node (ref "X1") (pin "GP9") (pinfunction "GP9_GP9") (pintype "bidirectional"))
    )
    (net (code "126") (name "unconnected-(X1-PadGP10)") (class "Default")
      (node (ref "X1") (pin "GP10") (pinfunction "GP10_GP10") (pintype "bidirectional"))
    )
    (net (code "127") (name "unconnected-(X1-PadGP16)") (class "Default")
      (node (ref "X1") (pin "GP16") (pinfunction "GP16_GP16") (pintype "bidirectional"))
    )
    (net (code "128") (name "unconnected-(X1-PadGP17)") (class "Default")
      (node (ref "X1") (pin "GP17") (pinfunction "GP17_GP17") (pintype "bidirectional"))
    )
    (net (code "129") (name "unconnected-(X1-PadRUN)") (class "Default")
      (node (ref "X1") (pin "RUN") (pinfunction "RUN_RUN") (pintype "bidirectional"))
    )
  )
)
